# SCH7_Main_Computer_PCIe.net
KiCad netlist of a schematic drawn in Altium Designer
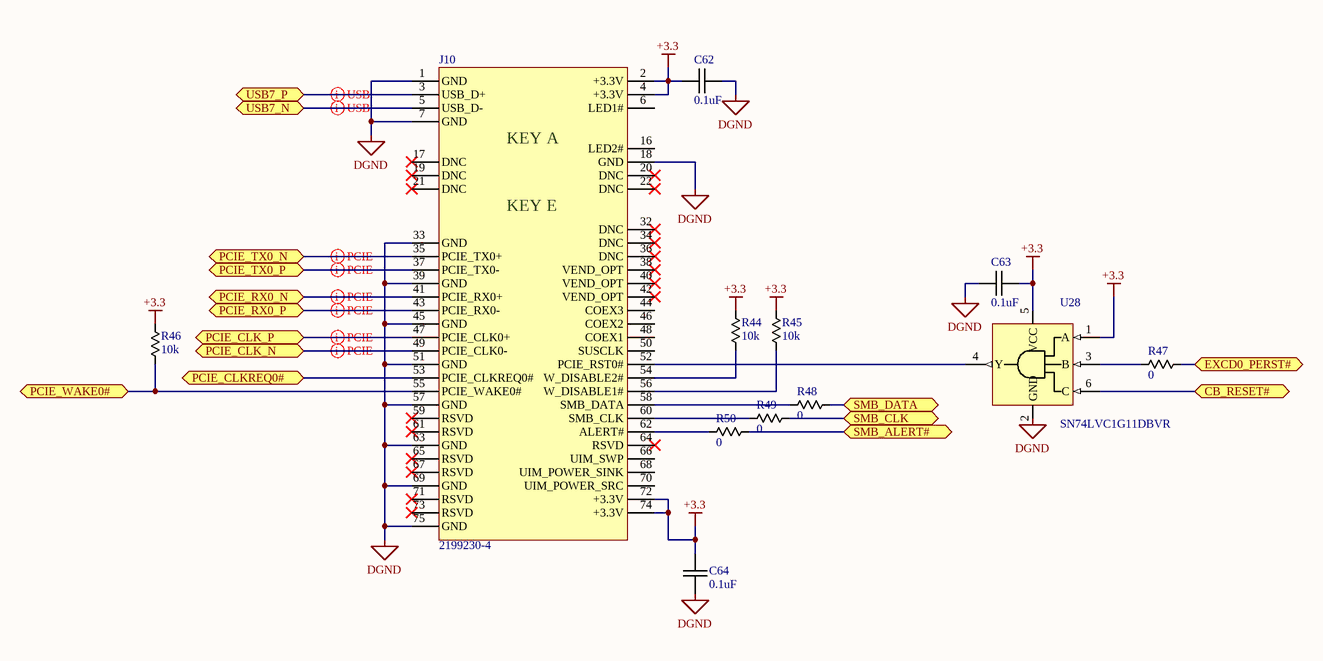
[diagram p0: SCH7_Main_Computer_PCIe.SchDoc]

(export (version "E")
  (design (tool "Eeschema 10.0.6"))
  (components
    (comp (ref "C62")
      (value "0.1uF")
      (footprint "chip_0603")
      (description "CAP, 0.1uF, ±10%, 16V, X7R, 0603")
      (fields (field (name "PART NUMBER") "CAP-00542") (field (name "TOLERANCE") "±10%"))
      (libsource (lib "Capacitors$") (part "CAP-00542"))
    )
    (comp (ref "C63")
      (value "0.1uF")
      (footprint "chip_0603")
      (description "CAP, 0.1uF, ±10%, 16V, X7R, 0603")
      (fields (field (name "PART NUMBER") "CAP-00542") (field (name "TOLERANCE") "±10%"))
      (libsource (lib "Capacitors$") (part "CAP-00542"))
    )
    (comp (ref "C64")
      (value "0.1uF")
      (footprint "chip_0603")
      (description "CAP, 0.1uF, ±10%, 16V, X7R, 0603")
      (fields (field (name "PART NUMBER") "CAP-00542") (field (name "TOLERANCE") "±10%"))
      (libsource (lib "Capacitors$") (part "CAP-00542"))
    )
    (comp (ref "J10")
      (value "2199230-4")
      (footprint "TE_CONN_2199230-4")
      (description "Card-Edge Socket, NGFF (M.2) E-Keyed, PCIe Card Socket")
      (fields (field (name "PART NUMBER") "CONN-00088") (field (name "MANUFACTURER") "TE Connectivity"))
      (libsource (lib "Connectors$") (part "CONN-00088"))
    )
    (comp (ref "R44")
      (value "10k")
      (footprint "chip_0603")
      (description "RES SMD 10K OHM 1% 1/4W 0603")
      (fields (field (name "PART NUMBER") "RES-00306") (field (name "TOLERANCE") "1%"))
      (libsource (lib "Resistors$") (part "RES-00306"))
    )
    (comp (ref "R45")
      (value "10k")
      (footprint "chip_0603")
      (description "RES SMD 10K OHM 1% 1/4W 0603")
      (fields (field (name "PART NUMBER") "RES-00306") (field (name "TOLERANCE") "1%"))
      (libsource (lib "Resistors$") (part "RES-00306"))
    )
    (comp (ref "R46")
      (value "10k")
      (footprint "chip_0603")
      (description "RES SMD 10K OHM 1% 1/4W 0603")
      (fields (field (name "PART NUMBER") "RES-00306") (field (name "TOLERANCE") "1%"))
      (libsource (lib "Resistors$") (part "RES-00306"))
    )
    (comp (ref "R47")
      (value "0")
      (footprint "chip_0805")
      (description "RES SMD 0 OHM 1/8W 0805 Thick Film")
      (fields (field (name "PART NUMBER") "RES-00720") (field (name "TOLERANCE") "Jumper"))
      (libsource (lib "Resistors$") (part "RES-00720"))
    )
    (comp (ref "R48")
      (value "0")
      (footprint "chip_0805")
      (description "RES SMD 0 OHM 1/8W 0805 Thick Film")
      (fields (field (name "PART NUMBER") "RES-00720") (field (name "TOLERANCE") "Jumper"))
      (libsource (lib "Resistors$") (part "RES-00720"))
    )
    (comp (ref "R49")
      (value "0")
      (footprint "chip_0805")
      (description "RES SMD 0 OHM 1/8W 0805 Thick Film")
      (fields (field (name "PART NUMBER") "RES-00720") (field (name "TOLERANCE") "Jumper"))
      (libsource (lib "Resistors$") (part "RES-00720"))
    )
    (comp (ref "R50")
      (value "0")
      (footprint "chip_0805")
      (description "RES SMD 0 OHM 1/8W 0805 Thick Film")
      (fields (field (name "PART NUMBER") "RES-00720") (field (name "TOLERANCE") "Jumper"))
      (libsource (lib "Resistors$") (part "RES-00720"))
    )
    (comp (ref "U28")
      (value "SN74LVC1G11DBVR")
      (footprint "sot-23-6")
      (description "IC, AND Gate, Single 3-Input, 1.65-5.5V, SOT-23-6")
      (fields (field (name "PART NUMBER") "LOGIC-00042") (field (name "MANUFACTURER") "TI"))
      (libsource (lib "Logic$") (part "LOGIC-00042"))
    )
  )
  (nets
    (net (code "1") (name "+3.3") (class "Default")
      (node (ref "C62") (pin "1") (pinfunction "1_1") (pintype "passive"))
      (node (ref "C63") (pin "2") (pinfunction "2_2") (pintype "passive"))
      (node (ref "C64") (pin "2") (pinfunction "2_2") (pintype "passive"))
      (node (ref "J10") (pin "2") (pinfunction "+3.3V_2") (pintype "passive"))
      (node (ref "J10") (pin "4") (pinfunction "+3.3V_4") (pintype "passive"))
      (node (ref "J10") (pin "72") (pinfunction "+3.3V_72") (pintype "passive"))
      (node (ref "J10") (pin "74") (pinfunction "+3.3V_74") (pintype "passive"))
      (node (ref "R44") (pin "1") (pinfunction "1_1") (pintype "passive"))
      (node (ref "R45") (pin "1") (pinfunction "1_1") (pintype "passive"))
      (node (ref "R46") (pin "1") (pinfunction "1_1") (pintype "passive"))
      (node (ref "U28") (pin "1") (pinfunction "A_1") (pintype "input"))
      (node (ref "U28") (pin "5") (pinfunction "VCC_5") (pintype "power_in"))
    )
    (net (code "2") (name "/CB_RESET#") (class "Default")
      (node (ref "U28") (pin "6") (pinfunction "C_6") (pintype "input"))
    )
    (net (code "3") (name "/EXCD0_PERST#") (class "Default")
      (node (ref "R47") (pin "1") (pinfunction "1_1") (pintype "passive"))
    )
    (net (code "4") (name "/PCIE_CLKREQ0#") (class "Default")
      (node (ref "J10") (pin "53") (pinfunction "PCIE_CLKREQ0#_53") (pintype "passive"))
    )
    (net (code "5") (name "/PCIE_CLK_N") (class "Default")
      (node (ref "J10") (pin "49") (pinfunction "PCIE_CLK0-_49") (pintype "passive"))
    )
    (net (code "6") (name "/PCIE_CLK_P") (class "Default")
      (node (ref "J10") (pin "47") (pinfunction "PCIE_CLK0+_47") (pintype "passive"))
    )
    (net (code "7") (name "/PCIE_RX0_N") (class "Default")
      (node (ref "J10") (pin "41") (pinfunction "PCIE_RX0+_41") (pintype "passive"))
    )
    (net (code "8") (name "/PCIE_RX0_P") (class "Default")
      (node (ref "J10") (pin "43") (pinfunction "PCIE_RX0-_43") (pintype "passive"))
    )
    (net (code "9") (name "/PCIE_TX0_N") (class "Default")
      (node (ref "J10") (pin "35") (pinfunction "PCIE_TX0+_35") (pintype "passive"))
    )
    (net (code "10") (name "/PCIE_TX0_P") (class "Default")
      (node (ref "J10") (pin "37") (pinfunction "PCIE_TX0-_37") (pintype "passive"))
    )
    (net (code "11") (name "/PCIE_WAKE0#") (class "Default")
      (node (ref "J10") (pin "55") (pinfunction "PCIE_WAKE0#_55") (pintype "passive"))
      (node (ref "R46") (pin "2") (pinfunction "2_2") (pintype "passive"))
    )
    (net (code "12") (name "/SMB_ALERT#") (class "Default")
      (node (ref "R50") (pin "1") (pinfunction "1_1") (pintype "passive"))
    )
    (net (code "13") (name "/SMB_CLK") (class "Default")
      (node (ref "R49") (pin "1") (pinfunction "1_1") (pintype "passive"))
    )
    (net (code "14") (name "/SMB_DATA") (class "Default")
      (node (ref "R48") (pin "1") (pinfunction "1_1") (pintype "passive"))
    )
    (net (code "15") (name "/USB7_N") (class "Default")
      (node (ref "J10") (pin "5") (pinfunction "USB_D-_5") (pintype "passive"))
    )
    (net (code "16") (name "/USB7_P") (class "Default")
      (node (ref "J10") (pin "3") (pinfunction "USB_D+_3") (pintype "passive"))
    )
    (net (code "17") (name "DGND") (class "Default")
      (node (ref "C62") (pin "2") (pinfunction "2_2") (pintype "passive"))
      (node (ref "C63") (pin "1") (pinfunction "1_1") (pintype "passive"))
      (node (ref "C64") (pin "1") (pinfunction "1_1") (pintype "passive"))
      (node (ref "J10") (pin "1") (pinfunction "GND_1") (pintype "passive"))
      (node (ref "J10") (pin "18") (pinfunction "GND_18") (pintype "passive"))
      (node (ref "J10") (pin "33") (pinfunction "GND_33") (pintype "passive"))
      (node (ref "J10") (pin "39") (pinfunction "GND_39") (pintype "passive"))
      (node (ref "J10") (pin "45") (pinfunction "GND_45") (pintype "passive"))
      (node (ref "J10") (pin "51") (pinfunction "GND_51") (pintype "passive"))
      (node (ref "J10") (pin "57") (pinfunction "GND_57") (pintype "passive"))
      (node (ref "J10") (pin "63") (pinfunction "GND_63") (pintype "passive"))
      (node (ref "J10") (pin "69") (pinfunction "GND_69") (pintype "passive"))
      (node (ref "J10") (pin "7") (pinfunction "GND_7") (pintype "passive"))
      (node (ref "J10") (pin "75") (pinfunction "GND_75") (pintype "passive"))
      (node (ref "U28") (pin "2") (pinfunction "GND_2") (pintype "power_in"))
    )
    (net (code "18") (name "Net-(J10-ALERT#)") (class "Default")
      (node (ref "J10") (pin "62") (pinfunction "ALERT#_62") (pintype "passive"))
      (node (ref "R50") (pin "2") (pinfunction "2_2") (pintype "passive"))
    )
    (net (code "19") (name "Net-(J10-PCIE_RST0#)") (class "Default")
      (node (ref "J10") (pin "52") (pinfunction "PCIE_RST0#_52") (pintype "passive"))
      (node (ref "U28") (pin "4") (pinfunction "Y_4") (pintype "output"))
    )
    (net (code "20") (name "Net-(J10-SMB_CLK)") (class "Default")
      (node (ref "J10") (pin "60") (pinfunction "SMB_CLK_60") (pintype "passive"))
      (node (ref "R49") (pin "2") (pinfunction "2_2") (pintype "passive"))
    )
    (net (code "21") (name "Net-(J10-SMB_DATA)") (class "Default")
      (node (ref "J10") (pin "58") (pinfunction "SMB_DATA_58") (pintype "passive"))
      (node (ref "R48") (pin "2") (pinfunction "2_2") (pintype "passive"))
    )
    (net (code "22") (name "Net-(J10-W_DISABLE1#)") (class "Default")
      (node (ref "J10") (pin "56") (pinfunction "W_DISABLE1#_56") (pintype "passive"))
      (node (ref "R45") (pin "2") (pinfunction "2_2") (pintype "passive"))
    )
    (net (code "23") (name "Net-(J10-W_DISABLE2#)") (class "Default")
      (node (ref "J10") (pin "54") (pinfunction "W_DISABLE2#_54") (pintype "passive"))
      (node (ref "R44") (pin "2") (pinfunction "2_2") (pintype "passive"))
    )
    (net (code "24") (name "Net-(U28-B)") (class "Default")
      (node (ref "R47") (pin "2") (pinfunction "2_2") (pintype "passive"))
      (node (ref "U28") (pin "3") (pinfunction "B_3") (pintype "input"))
    )
    (net (code "25") (name "unconnected-(J10-COEX1-Pad48)") (class "Default")
      (node (ref "J10") (pin "48") (pinfunction "COEX1_48") (pintype "passive"))
    )
    (net (code "26") (name "unconnected-(J10-COEX2-Pad46)") (class "Default")
      (node (ref "J10") (pin "46") (pinfunction "COEX2_46") (pintype "passive"))
    )
    (net (code "27") (name "unconnected-(J10-COEX3-Pad44)") (class "Default")
      (node (ref "J10") (pin "44") (pinfunction "COEX3_44") (pintype "passive"))
    )
    (net (code "28") (name "unconnected-(J10-DNC-Pad17)") (class "Default")
      (node (ref "J10") (pin "17") (pinfunction "DNC_17") (pintype "passive+no_connect"))
    )
    (net (code "29") (name "unconnected-(J10-DNC-Pad19)") (class "Default")
      (node (ref "J10") (pin "19") (pinfunction "DNC_19") (pintype "passive+no_connect"))
    )
    (net (code "30") (name "unconnected-(J10-DNC-Pad20)") (class "Default")
      (node (ref "J10") (pin "20") (pinfunction "DNC_20") (pintype "passive+no_connect"))
    )
    (net (code "31") (name "unconnected-(J10-DNC-Pad21)") (class "Default")
      (node (ref "J10") (pin "21") (pinfunction "DNC_21") (pintype "passive+no_connect"))
    )
    (net (code "32") (name "unconnected-(J10-DNC-Pad22)") (class "Default")
      (node (ref "J10") (pin "22") (pinfunction "DNC_22") (pintype "passive+no_connect"))
    )
    (net (code "33") (name "unconnected-(J10-DNC-Pad32)") (class "Default")
      (node (ref "J10") (pin "32") (pinfunction "DNC_32") (pintype "passive+no_connect"))
    )
    (net (code "34") (name "unconnected-(J10-DNC-Pad34)") (class "Default")
      (node (ref "J10") (pin "34") (pinfunction "DNC_34") (pintype "passive+no_connect"))
    )
    (net (code "35") (name "unconnected-(J10-DNC-Pad36)") (class "Default")
      (node (ref "J10") (pin "36") (pinfunction "DNC_36") (pintype "passive+no_connect"))
    )
    (net (code "36") (name "unconnected-(J10-LED1#-Pad6)") (class "Default")
      (node (ref "J10") (pin "6") (pinfunction "LED1#_6") (pintype "passive"))
    )
    (net (code "37") (name "unconnected-(J10-LED2#-Pad16)") (class "Default")
      (node (ref "J10") (pin "16") (pinfunction "LED2#_16") (pintype "passive"))
    )
    (net (code "38") (name "unconnected-(J10-RSVD-Pad59)") (class "Default")
      (node (ref "J10") (pin "59") (pinfunction "RSVD_59") (pintype "passive+no_connect"))
    )
    (net (code "39") (name "unconnected-(J10-RSVD-Pad61)") (class "Default")
      (node (ref "J10") (pin "61") (pinfunction "RSVD_61") (pintype "passive+no_connect"))
    )
    (net (code "40") (name "unconnected-(J10-RSVD-Pad64)") (class "Default")
      (node (ref "J10") (pin "64") (pinfunction "RSVD_64") (pintype "passive+no_connect"))
    )
    (net (code "41") (name "unconnected-(J10-RSVD-Pad65)") (class "Default")
      (node (ref "J10") (pin "65") (pinfunction "RSVD_65") (pintype "passive+no_connect"))
    )
    (net (code "42") (name "unconnected-(J10-RSVD-Pad67)") (class "Default")
      (node (ref "J10") (pin "67") (pinfunction "RSVD_67") (pintype "passive+no_connect"))
    )
    (net (code "43") (name "unconnected-(J10-RSVD-Pad71)") (class "Default")
      (node (ref "J10") (pin "71") (pinfunction "RSVD_71") (pintype "passive+no_connect"))
    )
    (net (code "44") (name "unconnected-(J10-RSVD-Pad73)") (class "Default")
      (node (ref "J10") (pin "73") (pinfunction "RSVD_73") (pintype "passive+no_connect"))
    )
    (net (code "45") (name "unconnected-(J10-SUSCLK-Pad50)") (class "Default")
      (node (ref "J10") (pin "50") (pinfunction "SUSCLK_50") (pintype "passive"))
    )
    (net (code "46") (name "unconnected-(J10-UIM_POWER_SINK-Pad68)") (class "Default")
      (node (ref "J10") (pin "68") (pinfunction "UIM_POWER_SINK_68") (pintype "passive"))
    )
    (net (code "47") (name "unconnected-(J10-UIM_POWER_SRC-Pad70)") (class "Default")
      (node (ref "J10") (pin "70") (pinfunction "UIM_POWER_SRC_70") (pintype "passive"))
    )
    (net (code "48") (name "unconnected-(J10-UIM_SWP-Pad66)") (class "Default")
      (node (ref "J10") (pin "66") (pinfunction "UIM_SWP_66") (pintype "passive"))
    )
    (net (code "49") (name "unconnected-(J10-VEND_OPT-Pad38)") (class "Default")
      (node (ref "J10") (pin "38") (pinfunction "VEND_OPT_38") (pintype "passive+no_connect"))
    )
    (net (code "50") (name "unconnected-(J10-VEND_OPT-Pad40)") (class "Default")
      (node (ref "J10") (pin "40") (pinfunction "VEND_OPT_40") (pintype "passive+no_connect"))
    )
    (net (code "51") (name "unconnected-(J10-VEND_OPT-Pad42)") (class "Default")
      (node (ref "J10") (pin "42") (pinfunction "VEND_OPT_42") (pintype "passive+no_connect"))
    )
  )
)
